# SCH_cansat2025_2025-10-28.net
KiCad netlist of a schematic drawn in EasyEDA
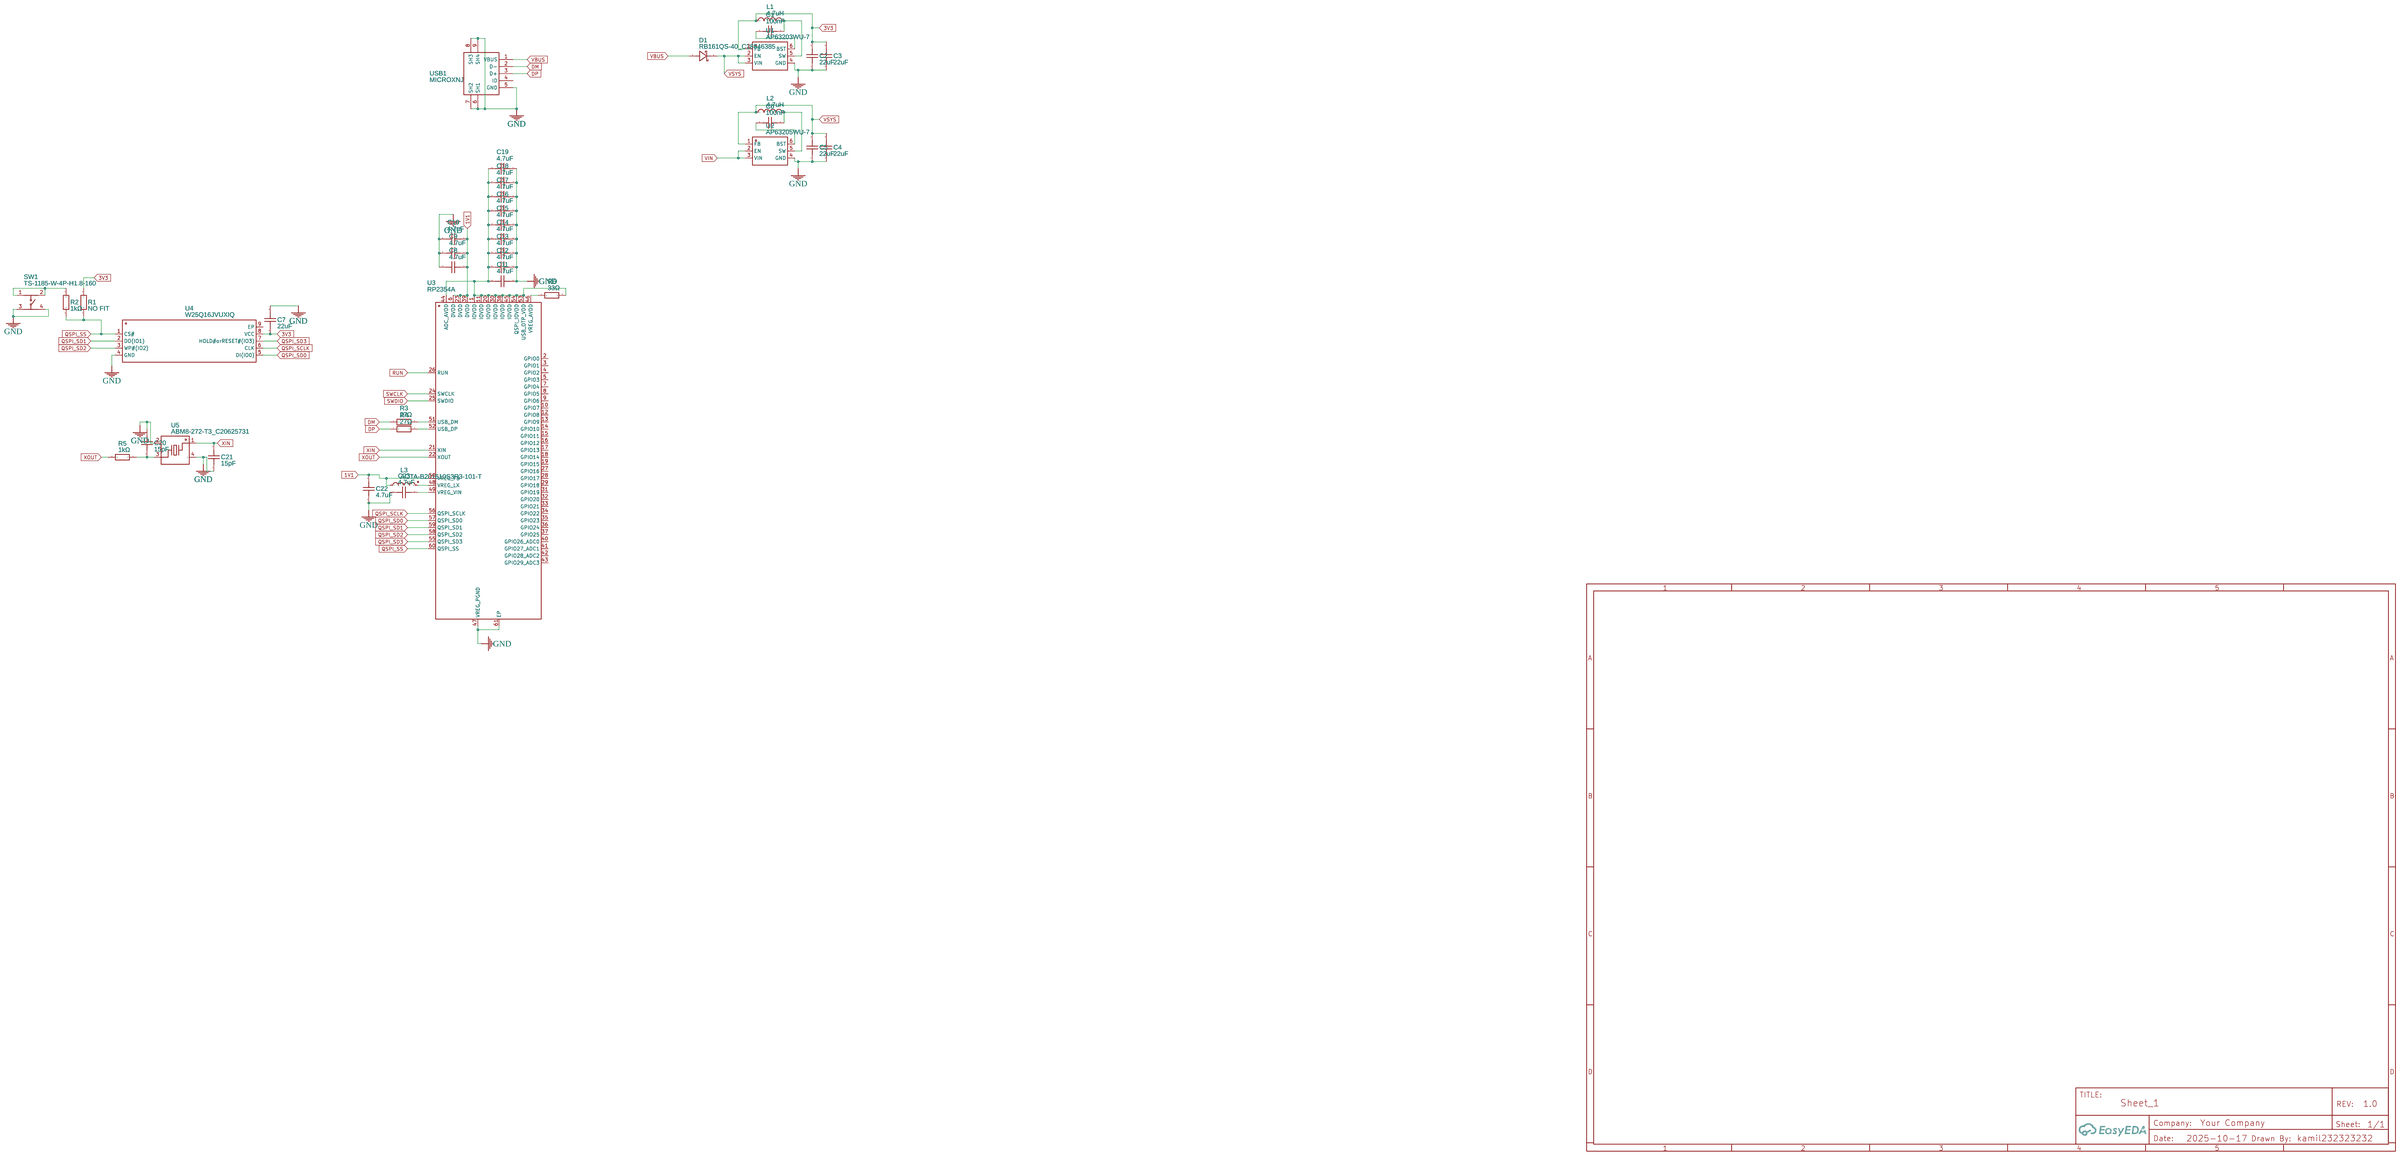
[diagram p0: schematic sheet]

(export (version "E")
  (design (tool "Eeschema 10.0.6"))
  (components
    (comp (ref "C1")
      (value "100nF")
      (fields
        (field (name "Manufacturer Part") "FCC0402B104K160AT")
        (field (name "Manufacturer") "FOJAN(富捷)")
      )
      (libsource (lib "") (part "FCC0402B104K160AT"))
    )
    (comp (ref "C2")
      (value "22uF")
      (fields
        (field (name "Manufacturer Part") "GRM155R60J226ME11D")
        (field (name "Manufacturer") "muRata(村田)")
      )
      (libsource (lib "") (part "GRM155R60J226ME11D"))
    )
    (comp (ref "C3")
      (value "22uF")
      (fields
        (field (name "Manufacturer Part") "GRM155R60J226ME11D")
        (field (name "Manufacturer") "muRata(村田)")
      )
      (libsource (lib "") (part "GRM155R60J226ME11D"))
    )
    (comp (ref "C4")
      (value "22uF")
      (fields
        (field (name "Manufacturer Part") "GRM155R60J226ME11D")
        (field (name "Manufacturer") "muRata(村田)")
      )
      (libsource (lib "") (part "GRM155R60J226ME11D"))
    )
    (comp (ref "C5")
      (value "22uF")
      (fields
        (field (name "Manufacturer Part") "GRM155R60J226ME11D")
        (field (name "Manufacturer") "muRata(村田)")
      )
      (libsource (lib "") (part "GRM155R60J226ME11D"))
    )
    (comp (ref "C6")
      (value "100nF")
      (fields
        (field (name "Manufacturer Part") "FCC0402B104K160AT")
        (field (name "Manufacturer") "FOJAN(富捷)")
      )
      (libsource (lib "") (part "FCC0402B104K160AT"))
    )
    (comp (ref "C7")
      (value "22uF")
      (fields
        (field (name "Manufacturer Part") "GRM155R60J226ME11D")
        (field (name "Manufacturer") "muRata(村田)")
      )
      (libsource (lib "") (part "GRM155R60J226ME11D"))
    )
    (comp (ref "C8")
      (value "4.7uF")
      (fields
        (field (name "Manufacturer Part") "CL05A475MP5NRNC")
        (field (name "Manufacturer") "SAMSUNG(三星)")
      )
      (libsource (lib "") (part "CL05A475MP5NRNC"))
    )
    (comp (ref "C9")
      (value "4.7uF")
      (fields
        (field (name "Manufacturer Part") "CL05A475MP5NRNC")
        (field (name "Manufacturer") "SAMSUNG(三星)")
      )
      (libsource (lib "") (part "CL05A475MP5NRNC"))
    )
    (comp (ref "C10")
      (value "4.7uF")
      (fields
        (field (name "Manufacturer Part") "CL05A475MP5NRNC")
        (field (name "Manufacturer") "SAMSUNG(三星)")
      )
      (libsource (lib "") (part "CL05A475MP5NRNC"))
    )
    (comp (ref "C11")
      (value "4.7uF")
      (fields
        (field (name "Manufacturer Part") "CL05A475MP5NRNC")
        (field (name "Manufacturer") "SAMSUNG(三星)")
      )
      (libsource (lib "") (part "CL05A475MP5NRNC"))
    )
    (comp (ref "C12")
      (value "4.7uF")
      (fields
        (field (name "Manufacturer Part") "CL05A475MP5NRNC")
        (field (name "Manufacturer") "SAMSUNG(三星)")
      )
      (libsource (lib "") (part "CL05A475MP5NRNC"))
    )
    (comp (ref "C13")
      (value "4.7uF")
      (fields
        (field (name "Manufacturer Part") "CL05A475MP5NRNC")
        (field (name "Manufacturer") "SAMSUNG(三星)")
      )
      (libsource (lib "") (part "CL05A475MP5NRNC"))
    )
    (comp (ref "C14")
      (value "4.7uF")
      (fields
        (field (name "Manufacturer Part") "CL05A475MP5NRNC")
        (field (name "Manufacturer") "SAMSUNG(三星)")
      )
      (libsource (lib "") (part "CL05A475MP5NRNC"))
    )
    (comp (ref "C15")
      (value "4.7uF")
      (fields
        (field (name "Manufacturer Part") "CL05A475MP5NRNC")
        (field (name "Manufacturer") "SAMSUNG(三星)")
      )
      (libsource (lib "") (part "CL05A475MP5NRNC"))
    )
    (comp (ref "C16")
      (value "4.7uF")
      (fields
        (field (name "Manufacturer Part") "CL05A475MP5NRNC")
        (field (name "Manufacturer") "SAMSUNG(三星)")
      )
      (libsource (lib "") (part "CL05A475MP5NRNC"))
    )
    (comp (ref "C17")
      (value "4.7uF")
      (fields
        (field (name "Manufacturer Part") "CL05A475MP5NRNC")
        (field (name "Manufacturer") "SAMSUNG(三星)")
      )
      (libsource (lib "") (part "CL05A475MP5NRNC"))
    )
    (comp (ref "C18")
      (value "4.7uF")
      (fields
        (field (name "Manufacturer Part") "CL05A475MP5NRNC")
        (field (name "Manufacturer") "SAMSUNG(三星)")
      )
      (libsource (lib "") (part "CL05A475MP5NRNC"))
    )
    (comp (ref "C19")
      (value "4.7uF")
      (fields
        (field (name "Manufacturer Part") "CL05A475MP5NRNC")
        (field (name "Manufacturer") "SAMSUNG(三星)")
      )
      (libsource (lib "") (part "CL05A475MP5NRNC"))
    )
    (comp (ref "C20")
      (value "15pF")
      (fields
        (field (name "Manufacturer Part") "CL05C150JB5NNNC")
        (field (name "Manufacturer") "SAMSUNG(三星)")
      )
      (libsource (lib "") (part "CL05C150JB5NNNC"))
    )
    (comp (ref "C21")
      (value "15pF")
      (fields
        (field (name "Manufacturer Part") "CL05C150JB5NNNC")
        (field (name "Manufacturer") "SAMSUNG(三星)")
      )
      (libsource (lib "") (part "CL05C150JB5NNNC"))
    )
    (comp (ref "C22")
      (value "4.7uF")
      (fields
        (field (name "Manufacturer Part") "CL05A475MP5NRNC")
        (field (name "Manufacturer") "SAMSUNG(三星)")
      )
      (libsource (lib "") (part "CL05A475MP5NRNC_1"))
    )
    (comp (ref "C23")
      (value "4.7uF")
      (fields
        (field (name "Manufacturer Part") "CL05A475MP5NRNC")
        (field (name "Manufacturer") "SAMSUNG(三星)")
      )
      (libsource (lib "") (part "CL05A475MP5NRNC_2"))
    )
    (comp (ref "D1")
      (value "RB161QS-40_C28646385")
      (fields (field (name "Manufacturer Part") "RB161QS-40") (field (name "Manufacturer") "TECH PUBLIC(台舟)"))
      (libsource (lib "") (part "RB161QS-40_C28646385"))
    )
    (comp (ref "L1")
      (value "4.7uH")
      (fields (field (name "Manufacturer Part") "CMI201209U4R7KT") (field (name "Manufacturer") "FH(风华)"))
      (libsource (lib "") (part "CMI201209U4R7KT_1"))
    )
    (comp (ref "L2")
      (value "4.7uH")
      (fields (field (name "Manufacturer Part") "CMI201209U4R7KT") (field (name "Manufacturer") "FH(风华)"))
      (libsource (lib "") (part "CMI201209U4R7KT"))
    )
    (comp (ref "L3")
      (value "AOTA-B201610S3R3-101-T")
      (fields (field (name "Manufacturer") "ABRACON"))
      (libsource (lib "") (part "AOTA-B201610S3R3-101-T"))
    )
    (comp (ref "R1")
      (value "NO FIT")
      (fields
        (field (name "Manufacturer Part") "0402WGF1002TCE")
        (field (name "Manufacturer") "UNI-ROYAL(厚声)")
      )
      (libsource (lib "") (part "0402WGF1002TCE"))
    )
    (comp (ref "R2")
      (value "1kΩ")
      (fields
        (field (name "Manufacturer Part") "0402WGF1001TCE")
        (field (name "Manufacturer") "UNI-ROYAL(厚声)")
      )
      (libsource (lib "") (part "0402WGF1001TCE_1"))
    )
    (comp (ref "R3")
      (value "27Ω")
      (fields
        (field (name "Manufacturer Part") "0402WGF270JTCE")
        (field (name "Manufacturer") "UNI-ROYAL(厚声)")
      )
      (libsource (lib "") (part "0402WGF270JTCE"))
    )
    (comp (ref "R4")
      (value "27Ω")
      (fields
        (field (name "Manufacturer Part") "0402WGF270JTCE")
        (field (name "Manufacturer") "UNI-ROYAL(厚声)")
      )
      (libsource (lib "") (part "0402WGF270JTCE"))
    )
    (comp (ref "R5")
      (value "1kΩ")
      (fields
        (field (name "Manufacturer Part") "0402WGF1001TCE")
        (field (name "Manufacturer") "UNI-ROYAL(厚声)")
      )
      (libsource (lib "") (part "0402WGF1001TCE"))
    )
    (comp (ref "R6")
      (value "33Ω")
      (fields
        (field (name "Manufacturer Part") "0402WGF330JTCE")
        (field (name "Manufacturer") "UNI-ROYAL(厚声)")
      )
      (libsource (lib "") (part "0402WGF330JTCE"))
    )
    (comp (ref "SW1")
      (value "TS-1185-W-4P-H1.8-160")
      (fields (field (name "Manufacturer") "CAX(创都)"))
      (libsource (lib "") (part "TS-1185-W-4P-H1.8-160"))
    )
    (comp (ref "U1")
      (value "AP63203WU-7")
      (fields (field (name "Manufacturer") "DIODES(美台)"))
      (libsource (lib "") (part "AP63203WU-7"))
    )
    (comp (ref "U2")
      (value "AP63205WU-7")
      (fields (field (name "Manufacturer") "DIODES(美台)"))
      (libsource (lib "") (part "AP63205WU-7"))
    )
    (comp (ref "U3")
      (value "RP2354A")
      (fields (field (name "Manufacturer") "Raspberry Pi(树莓派)"))
      (libsource (lib "") (part "RP2354A"))
    )
    (comp (ref "U4")
      (value "W25Q16JVUXIQ")
      (fields (field (name "Manufacturer") "Winbond(华邦)"))
      (libsource (lib "") (part "W25Q16JVUXIQ"))
    )
    (comp (ref "U5")
      (value "ABM8-272-T3_C20625731")
      (fields (field (name "Manufacturer Part") "ABM8-272-T3") (field (name "Manufacturer") "ABRACON"))
      (libsource (lib "") (part "ABM8-272-T3_C20625731"))
    )
    (comp (ref "USB1")
      (value "MICROXNJ")
      (fields (field (name "Manufacturer Part") "MicroXNJ") (field (name "Manufacturer") "SHOU HAN(首韩)"))
      (libsource (lib "") (part "MICROXNJ"))
    )
  )
  (nets
    (net (code "1") (name "1V1") (class "Default")
      (node (ref "C10") (pin "1") (pinfunction "1_1") (pintype "unspecified"))
      (node (ref "C22") (pin "1") (pinfunction "1_1") (pintype "unspecified"))
      (node (ref "C8") (pin "1") (pinfunction "1_1") (pintype "unspecified"))
      (node (ref "C9") (pin "1") (pinfunction "1_1") (pintype "unspecified"))
      (node (ref "L3") (pin "1") (pinfunction "1_1") (pintype "unspecified"))
      (node (ref "U3") (pin "23") (pinfunction "DVDD_23") (pintype "unspecified"))
      (node (ref "U3") (pin "39") (pinfunction "DVDD_39") (pintype "unspecified"))
      (node (ref "U3") (pin "50") (pinfunction "VREG_FB_50") (pintype "unspecified"))
      (node (ref "U3") (pin "6") (pinfunction "DVDD_6") (pintype "unspecified"))
    )
    (net (code "2") (name "3V3") (class "Default")
      (node (ref "C2") (pin "2") (pinfunction "2_2") (pintype "unspecified"))
      (node (ref "C3") (pin "2") (pinfunction "2_2") (pintype "unspecified"))
      (node (ref "C7") (pin "1") (pinfunction "1_1") (pintype "unspecified"))
      (node (ref "L1") (pin "1") (pinfunction "1_1") (pintype "unspecified"))
      (node (ref "R1") (pin "2") (pinfunction "2_2") (pintype "input"))
      (node (ref "U1") (pin "1") (pinfunction "FB_1") (pintype "unspecified"))
      (node (ref "U4") (pin "8") (pinfunction "VCC_8") (pintype "unspecified"))
    )
    (net (code "3") (name "DM") (class "Default")
      (node (ref "R3") (pin "1") (pinfunction "1_1") (pintype "input"))
      (node (ref "USB1") (pin "2") (pinfunction "D-_2") (pintype "unspecified"))
    )
    (net (code "4") (name "DP") (class "Default")
      (node (ref "R4") (pin "1") (pinfunction "1_1") (pintype "input"))
      (node (ref "USB1") (pin "3") (pinfunction "D+_3") (pintype "unspecified"))
    )
    (net (code "5") (name "GND") (class "Default")
      (node (ref "C10") (pin "2") (pinfunction "2_2") (pintype "unspecified"))
      (node (ref "C11") (pin "1") (pinfunction "1_1") (pintype "unspecified"))
      (node (ref "C12") (pin "1") (pinfunction "1_1") (pintype "unspecified"))
      (node (ref "C13") (pin "1") (pinfunction "1_1") (pintype "unspecified"))
      (node (ref "C14") (pin "1") (pinfunction "1_1") (pintype "unspecified"))
      (node (ref "C15") (pin "1") (pinfunction "1_1") (pintype "unspecified"))
      (node (ref "C16") (pin "1") (pinfunction "1_1") (pintype "unspecified"))
      (node (ref "C17") (pin "1") (pinfunction "1_1") (pintype "unspecified"))
      (node (ref "C18") (pin "1") (pinfunction "1_1") (pintype "unspecified"))
      (node (ref "C19") (pin "1") (pinfunction "1_1") (pintype "unspecified"))
      (node (ref "C2") (pin "1") (pinfunction "1_1") (pintype "unspecified"))
      (node (ref "C20") (pin "2") (pinfunction "2_2") (pintype "unspecified"))
      (node (ref "C21") (pin "1") (pinfunction "1_1") (pintype "unspecified"))
      (node (ref "C22") (pin "2") (pinfunction "2_2") (pintype "unspecified"))
      (node (ref "C23") (pin "1") (pinfunction "1_1") (pintype "unspecified"))
      (node (ref "C3") (pin "1") (pinfunction "1_1") (pintype "unspecified"))
      (node (ref "C4") (pin "1") (pinfunction "1_1") (pintype "unspecified"))
      (node (ref "C5") (pin "1") (pinfunction "1_1") (pintype "unspecified"))
      (node (ref "C7") (pin "2") (pinfunction "2_2") (pintype "unspecified"))
      (node (ref "C8") (pin "2") (pinfunction "2_2") (pintype "unspecified"))
      (node (ref "C9") (pin "2") (pinfunction "2_2") (pintype "unspecified"))
      (node (ref "SW1") (pin "3") (pinfunction "3_3") (pintype "unspecified"))
      (node (ref "SW1") (pin "4") (pinfunction "4_4") (pintype "unspecified"))
      (node (ref "U1") (pin "4") (pinfunction "GND_4") (pintype "unspecified"))
      (node (ref "U2") (pin "4") (pinfunction "GND_4") (pintype "unspecified"))
      (node (ref "U3") (pin "47") (pinfunction "VREG_PGND_47") (pintype "unspecified"))
      (node (ref "U3") (pin "61") (pinfunction "EP_61") (pintype "unspecified"))
      (node (ref "U4") (pin "4") (pinfunction "GND_4") (pintype "unspecified"))
      (node (ref "U5") (pin "2") (pinfunction "GND_2") (pintype "input"))
      (node (ref "U5") (pin "4") (pinfunction "GND_4") (pintype "input"))
      (node (ref "USB1") (pin "5") (pinfunction "GND_5") (pintype "unspecified"))
      (node (ref "USB1") (pin "6") (pinfunction "SH1_6") (pintype "unspecified"))
      (node (ref "USB1") (pin "7") (pinfunction "SH2_7") (pintype "unspecified"))
      (node (ref "USB1") (pin "8") (pinfunction "SH3_8") (pintype "unspecified"))
      (node (ref "USB1") (pin "9") (pinfunction "SH4_9") (pintype "unspecified"))
    )
    (net (code "6") (name "Net-(C20-Pad1)") (class "Default")
      (node (ref "C20") (pin "1") (pinfunction "1_1") (pintype "unspecified"))
      (node (ref "R5") (pin "1") (pinfunction "1_1") (pintype "input"))
      (node (ref "U5") (pin "3") (pinfunction "3_3") (pintype "input"))
    )
    (net (code "7") (name "Net-(R2-Pad2)") (class "Default")
      (node (ref "R2") (pin "2") (pinfunction "2_2") (pintype "input"))
      (node (ref "SW1") (pin "1") (pinfunction "1_1") (pintype "unspecified"))
      (node (ref "SW1") (pin "2") (pinfunction "2_2") (pintype "unspecified"))
    )
    (net (code "8") (name "Net-(U1-BST)") (class "Default")
      (node (ref "C1") (pin "1") (pinfunction "1_1") (pintype "unspecified"))
      (node (ref "U1") (pin "6") (pinfunction "BST_6") (pintype "unspecified"))
    )
    (net (code "9") (name "Net-(U1-SW)") (class "Default")
      (node (ref "C1") (pin "2") (pinfunction "2_2") (pintype "unspecified"))
      (node (ref "L1") (pin "2") (pinfunction "2_2") (pintype "unspecified"))
      (node (ref "U1") (pin "5") (pinfunction "SW_5") (pintype "unspecified"))
    )
    (net (code "10") (name "Net-(U2-BST)") (class "Default")
      (node (ref "C6") (pin "1") (pinfunction "1_1") (pintype "unspecified"))
      (node (ref "U2") (pin "6") (pinfunction "BST_6") (pintype "unspecified"))
    )
    (net (code "11") (name "Net-(U2-SW)") (class "Default")
      (node (ref "C6") (pin "2") (pinfunction "2_2") (pintype "unspecified"))
      (node (ref "L2") (pin "2") (pinfunction "2_2") (pintype "unspecified"))
      (node (ref "U2") (pin "5") (pinfunction "SW_5") (pintype "unspecified"))
    )
    (net (code "12") (name "Net-(U3-ADC_AVDD)") (class "Default")
      (node (ref "C11") (pin "2") (pinfunction "2_2") (pintype "unspecified"))
      (node (ref "C12") (pin "2") (pinfunction "2_2") (pintype "unspecified"))
      (node (ref "C13") (pin "2") (pinfunction "2_2") (pintype "unspecified"))
      (node (ref "C14") (pin "2") (pinfunction "2_2") (pintype "unspecified"))
      (node (ref "C15") (pin "2") (pinfunction "2_2") (pintype "unspecified"))
      (node (ref "C16") (pin "2") (pinfunction "2_2") (pintype "unspecified"))
      (node (ref "C17") (pin "2") (pinfunction "2_2") (pintype "unspecified"))
      (node (ref "C18") (pin "2") (pinfunction "2_2") (pintype "unspecified"))
      (node (ref "C19") (pin "2") (pinfunction "2_2") (pintype "unspecified"))
      (node (ref "R6") (pin "2") (pinfunction "2_2") (pintype "input"))
      (node (ref "U3") (pin "1") (pinfunction "IOVDD_1") (pintype "unspecified"))
      (node (ref "U3") (pin "11") (pinfunction "IOVDD_11") (pintype "unspecified"))
      (node (ref "U3") (pin "20") (pinfunction "IOVDD_20") (pintype "unspecified"))
      (node (ref "U3") (pin "30") (pinfunction "IOVDD_30") (pintype "unspecified"))
      (node (ref "U3") (pin "38") (pinfunction "IOVDD_38") (pintype "unspecified"))
      (node (ref "U3") (pin "44") (pinfunction "ADC_AVDD_44") (pintype "unspecified"))
      (node (ref "U3") (pin "45") (pinfunction "IOVDD_45") (pintype "unspecified"))
      (node (ref "U3") (pin "53") (pinfunction "USB_OTP_VDD_53") (pintype "unspecified"))
      (node (ref "U3") (pin "54") (pinfunction "QSPI_IOVDD_54") (pintype "unspecified"))
    )
    (net (code "13") (name "Net-(U3-USB_DM)") (class "Default")
      (node (ref "R3") (pin "2") (pinfunction "2_2") (pintype "input"))
      (node (ref "U3") (pin "51") (pinfunction "USB_DM_51") (pintype "unspecified"))
    )
    (net (code "14") (name "Net-(U3-USB_DP)") (class "Default")
      (node (ref "R4") (pin "2") (pinfunction "2_2") (pintype "input"))
      (node (ref "U3") (pin "52") (pinfunction "USB_DP_52") (pintype "unspecified"))
    )
    (net (code "15") (name "Net-(U3-VREG_AVDD)") (class "Default")
      (node (ref "R6") (pin "1") (pinfunction "1_1") (pintype "input"))
      (node (ref "U3") (pin "46") (pinfunction "VREG_AVDD_46") (pintype "unspecified"))
    )
    (net (code "16") (name "Net-(U3-VREG_LX)") (class "Default")
      (node (ref "L3") (pin "2") (pinfunction "2_2") (pintype "unspecified"))
      (node (ref "U3") (pin "48") (pinfunction "VREG_LX_48") (pintype "unspecified"))
    )
    (net (code "17") (name "Net-(U3-VREG_VIN)") (class "Default")
      (node (ref "C23") (pin "2") (pinfunction "2_2") (pintype "unspecified"))
      (node (ref "U3") (pin "49") (pinfunction "VREG_VIN_49") (pintype "unspecified"))
    )
    (net (code "18") (name "QSPI_SCLK") (class "Default")
      (node (ref "U3") (pin "56") (pinfunction "QSPI_SCLK_56") (pintype "unspecified"))
      (node (ref "U4") (pin "6") (pinfunction "CLK_6") (pintype "unspecified"))
    )
    (net (code "19") (name "QSPI_SD0") (class "Default")
      (node (ref "U3") (pin "57") (pinfunction "QSPI_SD0_57") (pintype "unspecified"))
      (node (ref "U4") (pin "5") (pinfunction "DI(IO0)_5") (pintype "unspecified"))
    )
    (net (code "20") (name "QSPI_SD1") (class "Default")
      (node (ref "U3") (pin "59") (pinfunction "QSPI_SD1_59") (pintype "unspecified"))
      (node (ref "U4") (pin "2") (pinfunction "DO(IO1)_2") (pintype "unspecified"))
    )
    (net (code "21") (name "QSPI_SD2") (class "Default")
      (node (ref "U3") (pin "58") (pinfunction "QSPI_SD2_58") (pintype "unspecified"))
      (node (ref "U4") (pin "3") (pinfunction "WP#(IO2)_3") (pintype "unspecified"))
    )
    (net (code "22") (name "QSPI_SD3") (class "Default")
      (node (ref "U3") (pin "55") (pinfunction "QSPI_SD3_55") (pintype "unspecified"))
      (node (ref "U4") (pin "7") (pinfunction "HOLD#orRESET#(IO3)_7") (pintype "unspecified"))
    )
    (net (code "23") (name "QSPI_SS") (class "Default")
      (node (ref "R1") (pin "1") (pinfunction "1_1") (pintype "input"))
      (node (ref "R2") (pin "1") (pinfunction "1_1") (pintype "input"))
      (node (ref "U3") (pin "60") (pinfunction "QSPI_SS_60") (pintype "unspecified"))
      (node (ref "U4") (pin "1") (pinfunction "CS#_1") (pintype "unspecified"))
    )
    (net (code "24") (name "RUN") (class "Default")
      (node (ref "U3") (pin "26") (pinfunction "RUN_26") (pintype "unspecified"))
    )
    (net (code "25") (name "SWCLK") (class "Default")
      (node (ref "U3") (pin "24") (pinfunction "SWCLK_24") (pintype "unspecified"))
    )
    (net (code "26") (name "SWDIO") (class "Default")
      (node (ref "U3") (pin "25") (pinfunction "SWDIO_25") (pintype "unspecified"))
    )
    (net (code "27") (name "VBUS") (class "Default")
      (node (ref "D1") (pin "2") (pinfunction "A_2") (pintype "unspecified"))
      (node (ref "USB1") (pin "1") (pinfunction "VBUS_1") (pintype "unspecified"))
    )
    (net (code "28") (name "VIN") (class "Default")
      (node (ref "U2") (pin "2") (pinfunction "EN_2") (pintype "unspecified"))
      (node (ref "U2") (pin "3") (pinfunction "VIN_3") (pintype "unspecified"))
    )
    (net (code "29") (name "VSYS") (class "Default")
      (node (ref "C4") (pin "2") (pinfunction "2_2") (pintype "unspecified"))
      (node (ref "C5") (pin "2") (pinfunction "2_2") (pintype "unspecified"))
      (node (ref "D1") (pin "1") (pinfunction "C_1") (pintype "unspecified"))
      (node (ref "L2") (pin "1") (pinfunction "1_1") (pintype "unspecified"))
      (node (ref "U1") (pin "2") (pinfunction "EN_2") (pintype "unspecified"))
      (node (ref "U1") (pin "3") (pinfunction "VIN_3") (pintype "unspecified"))
      (node (ref "U2") (pin "1") (pinfunction "FB_1") (pintype "unspecified"))
    )
    (net (code "30") (name "XIN") (class "Default")
      (node (ref "C21") (pin "2") (pinfunction "2_2") (pintype "unspecified"))
      (node (ref "U3") (pin "21") (pinfunction "XIN_21") (pintype "unspecified"))
      (node (ref "U5") (pin "1") (pinfunction "1_1") (pintype "input"))
    )
    (net (code "31") (name "XOUT") (class "Default")
      (node (ref "R5") (pin "2") (pinfunction "2_2") (pintype "input"))
      (node (ref "U3") (pin "22") (pinfunction "XOUT_22") (pintype "unspecified"))
    )
    (net (code "32") (name "unconnected-(U3-GPIO0-Pad2)") (class "Default")
      (node (ref "U3") (pin "2") (pinfunction "GPIO0_2") (pintype "unspecified"))
    )
    (net (code "33") (name "unconnected-(U3-GPIO1-Pad3)") (class "Default")
      (node (ref "U3") (pin "3") (pinfunction "GPIO1_3") (pintype "unspecified"))
    )
    (net (code "34") (name "unconnected-(U3-GPIO2-Pad4)") (class "Default")
      (node (ref "U3") (pin "4") (pinfunction "GPIO2_4") (pintype "unspecified"))
    )
    (net (code "35") (name "unconnected-(U3-GPIO3-Pad5)") (class "Default")
      (node (ref "U3") (pin "5") (pinfunction "GPIO3_5") (pintype "unspecified"))
    )
    (net (code "36") (name "unconnected-(U3-GPIO4-Pad7)") (class "Default")
      (node (ref "U3") (pin "7") (pinfunction "GPIO4_7") (pintype "unspecified"))
    )
    (net (code "37") (name "unconnected-(U3-GPIO5-Pad8)") (class "Default")
      (node (ref "U3") (pin "8") (pinfunction "GPIO5_8") (pintype "unspecified"))
    )
    (net (code "38") (name "unconnected-(U3-GPIO6-Pad9)") (class "Default")
      (node (ref "U3") (pin "9") (pinfunction "GPIO6_9") (pintype "unspecified"))
    )
    (net (code "39") (name "unconnected-(U3-GPIO7-Pad10)") (class "Default")
      (node (ref "U3") (pin "10") (pinfunction "GPIO7_10") (pintype "unspecified"))
    )
    (net (code "40") (name "unconnected-(U3-GPIO8-Pad12)") (class "Default")
      (node (ref "U3") (pin "12") (pinfunction "GPIO8_12") (pintype "unspecified"))
    )
    (net (code "41") (name "unconnected-(U3-GPIO9-Pad13)") (class "Default")
      (node (ref "U3") (pin "13") (pinfunction "GPIO9_13") (pintype "unspecified"))
    )
    (net (code "42") (name "unconnected-(U3-GPIO10-Pad14)") (class "Default")
      (node (ref "U3") (pin "14") (pinfunction "GPIO10_14") (pintype "unspecified"))
    )
    (net (code "43") (name "unconnected-(U3-GPIO11-Pad15)") (class "Default")
      (node (ref "U3") (pin "15") (pinfunction "GPIO11_15") (pintype "unspecified"))
    )
    (net (code "44") (name "unconnected-(U3-GPIO12-Pad16)") (class "Default")
      (node (ref "U3") (pin "16") (pinfunction "GPIO12_16") (pintype "unspecified"))
    )
    (net (code "45") (name "unconnected-(U3-GPIO13-Pad17)") (class "Default")
      (node (ref "U3") (pin "17") (pinfunction "GPIO13_17") (pintype "unspecified"))
    )
    (net (code "46") (name "unconnected-(U3-GPIO14-Pad18)") (class "Default")
      (node (ref "U3") (pin "18") (pinfunction "GPIO14_18") (pintype "unspecified"))
    )
    (net (code "47") (name "unconnected-(U3-GPIO15-Pad19)") (class "Default")
      (node (ref "U3") (pin "19") (pinfunction "GPIO15_19") (pintype "unspecified"))
    )
    (net (code "48") (name "unconnected-(U3-GPIO16-Pad27)") (class "Default")
      (node (ref "U3") (pin "27") (pinfunction "GPIO16_27") (pintype "unspecified"))
    )
    (net (code "49") (name "unconnected-(U3-GPIO17-Pad28)") (class "Default")
      (node (ref "U3") (pin "28") (pinfunction "GPIO17_28") (pintype "unspecified"))
    )
    (net (code "50") (name "unconnected-(U3-GPIO18-Pad29)") (class "Default")
      (node (ref "U3") (pin "29") (pinfunction "GPIO18_29") (pintype "unspecified"))
    )
    (net (code "51") (name "unconnected-(U3-GPIO19-Pad31)") (class "Default")
      (node (ref "U3") (pin "31") (pinfunction "GPIO19_31") (pintype "unspecified"))
    )
    (net (code "52") (name "unconnected-(U3-GPIO20-Pad32)") (class "Default")
      (node (ref "U3") (pin "32") (pinfunction "GPIO20_32") (pintype "unspecified"))
    )
    (net (code "53") (name "unconnected-(U3-GPIO21-Pad33)") (class "Default")
      (node (ref "U3") (pin "33") (pinfunction "GPIO21_33") (pintype "unspecified"))
    )
    (net (code "54") (name "unconnected-(U3-GPIO22-Pad34)") (class "Default")
      (node (ref "U3") (pin "34") (pinfunction "GPIO22_34") (pintype "unspecified"))
    )
    (net (code "55") (name "unconnected-(U3-GPIO23-Pad35)") (class "Default")
      (node (ref "U3") (pin "35") (pinfunction "GPIO23_35") (pintype "unspecified"))
    )
    (net (code "56") (name "unconnected-(U3-GPIO24-Pad36)") (class "Default")
      (node (ref "U3") (pin "36") (pinfunction "GPIO24_36") (pintype "unspecified"))
    )
    (net (code "57") (name "unconnected-(U3-GPIO25-Pad37)") (class "Default")
      (node (ref "U3") (pin "37") (pinfunction "GPIO25_37") (pintype "unspecified"))
    )
    (net (code "58") (name "unconnected-(U3-GPIO26_ADC0-Pad40)") (class "Default")
      (node (ref "U3") (pin "40") (pinfunction "GPIO26_ADC0_40") (pintype "unspecified"))
    )
    (net (code "59") (name "unconnected-(U3-GPIO27_ADC1-Pad41)") (class "Default")
      (node (ref "U3") (pin "41") (pinfunction "GPIO27_ADC1_41") (pintype "unspecified"))
    )
    (net (code "60") (name "unconnected-(U3-GPIO28_ADC2-Pad42)") (class "Default")
      (node (ref "U3") (pin "42") (pinfunction "GPIO28_ADC2_42") (pintype "unspecified"))
    )
    (net (code "61") (name "unconnected-(U3-GPIO29_ADC3-Pad43)") (class "Default")
      (node (ref "U3") (pin "43") (pinfunction "GPIO29_ADC3_43") (pintype "unspecified"))
    )
    (net (code "62") (name "unconnected-(U4-EP-Pad9)") (class "Default")
      (node (ref "U4") (pin "9") (pinfunction "EP_9") (pintype "unspecified"))
    )
    (net (code "63") (name "unconnected-(USB1-ID-Pad4)") (class "Default")
      (node (ref "USB1") (pin "4") (pinfunction "ID_4") (pintype "unspecified"))
    )
  )
)
